# CAM.net
KiCad netlist of a schematic drawn in Altium Designer
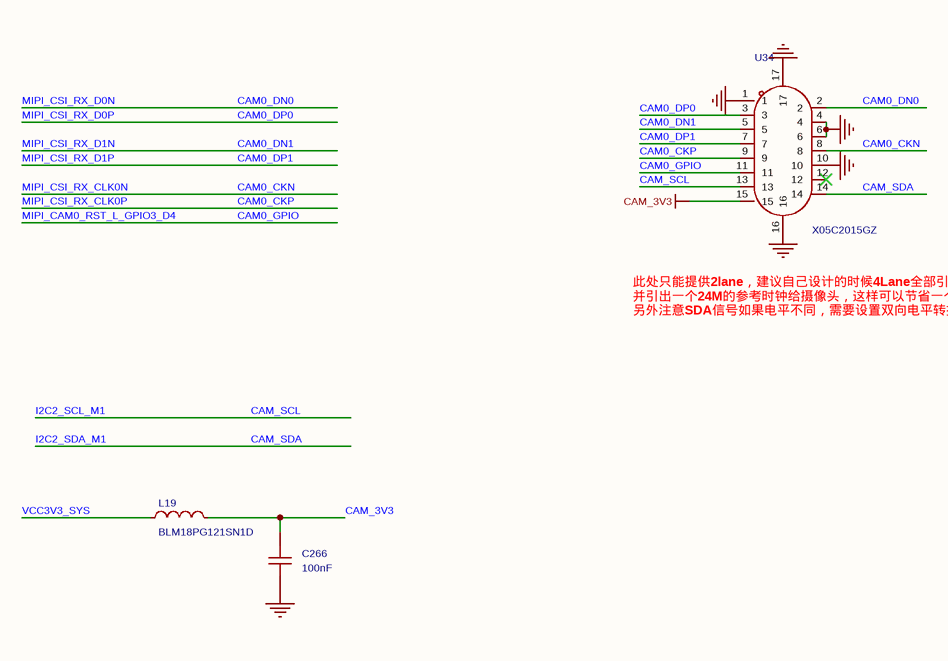
[diagram p0: CAM.schdoc]

(export (version "E")
  (design (tool "Eeschema 10.0.6"))
  (components
    (comp (ref "C266")
      (value "100nF")
      (footprint "C0603")
      (libsource (lib "altium-import") (part "root_1_CAP_0603_"))
    )
    (comp (ref "L19")
      (value "BLM18PG121SN1D")
      (footprint "L0603")
      (description "标称阻抗@测试频率:120Ω@100MHz;误差:±25%;直流电阻(RDC):50mΩ;")
      (fields (field (name "MANUFACTURER") "muRata(村田)") (field (name "TOLERANCE") "±25%"))
      (libsource (lib "altium-import") (part "root_0_BLM18PG121SN1D_"))
    )
    (comp (ref "U34")
      (value "X05C2015GZ")
      (footprint "FPC-SMD_15P-P0.50_XKB_X05C2015GZ")
      (description "锁定特性:抽屉式;触点类型:单侧触点/垂直;触点数量:15P;间距:0.5mm;安装方式:立贴;工作温度:-40℃~+85℃;")
      (fields (field (name "MANUFACTURER") "XKB Connection(中国星坤)"))
      (libsource (lib "altium-import") (part "root_0_X05C2015GZ_"))
    )
  )
  (nets
    (net (code "1") (name "/CAM0_CKN") (class "Default")
      (node (ref "U34") (pin "8") (pinfunction "8_8") (pintype "passive"))
    )
    (net (code "2") (name "/CAM0_CKP") (class "Default")
      (node (ref "U34") (pin "9") (pinfunction "9_9") (pintype "passive"))
    )
    (net (code "3") (name "/CAM0_DN0") (class "Default")
      (node (ref "U34") (pin "2") (pinfunction "2_2") (pintype "passive"))
    )
    (net (code "4") (name "/CAM0_DN1") (class "Default")
      (node (ref "U34") (pin "5") (pinfunction "5_5") (pintype "passive"))
    )
    (net (code "5") (name "/CAM0_DP0") (class "Default")
      (node (ref "U34") (pin "3") (pinfunction "3_3") (pintype "passive"))
    )
    (net (code "6") (name "/CAM0_DP1") (class "Default")
      (node (ref "U34") (pin "7") (pinfunction "7_7") (pintype "passive"))
    )
    (net (code "7") (name "/CAM0_GPIO") (class "Default")
      (node (ref "U34") (pin "11") (pinfunction "11_11") (pintype "passive"))
    )
    (net (code "8") (name "/CAM_SCL") (class "Default")
      (node (ref "U34") (pin "13") (pinfunction "13_13") (pintype "passive"))
    )
    (net (code "9") (name "/CAM_SDA") (class "Default")
      (node (ref "U34") (pin "14") (pinfunction "14_14") (pintype "passive"))
    )
    (net (code "10") (name "/VCC3V3_SYS") (class "Default")
      (node (ref "L19") (pin "1") (pinfunction "1_1") (pintype "passive"))
    )
    (net (code "11") (name "CAM_3V3") (class "Default")
      (node (ref "C266") (pin "2") (pinfunction "2_2") (pintype "passive"))
      (node (ref "L19") (pin "2") (pinfunction "2_2") (pintype "passive"))
      (node (ref "U34") (pin "15") (pinfunction "15_15") (pintype "passive"))
    )
    (net (code "12") (name "GND") (class "Default")
      (node (ref "C266") (pin "1") (pinfunction "1_1") (pintype "passive"))
      (node (ref "U34") (pin "1") (pinfunction "1_1") (pintype "passive"))
      (node (ref "U34") (pin "10") (pinfunction "10_10") (pintype "passive"))
      (node (ref "U34") (pin "16") (pinfunction "16_16") (pintype "passive"))
      (node (ref "U34") (pin "17") (pinfunction "17_17") (pintype "passive"))
      (node (ref "U34") (pin "4") (pinfunction "4_4") (pintype "passive"))
      (node (ref "U34") (pin "6") (pinfunction "6_6") (pintype "passive"))
    )
    (net (code "13") (name "unconnected-(U34-Pad12)") (class "Default")
      (node (ref "U34") (pin "12") (pinfunction "12_12") (pintype "passive+no_connect"))
    )
  )
)
